# Pallette_Rev1.net
KiCad netlist of a schematic drawn in Altium Designer
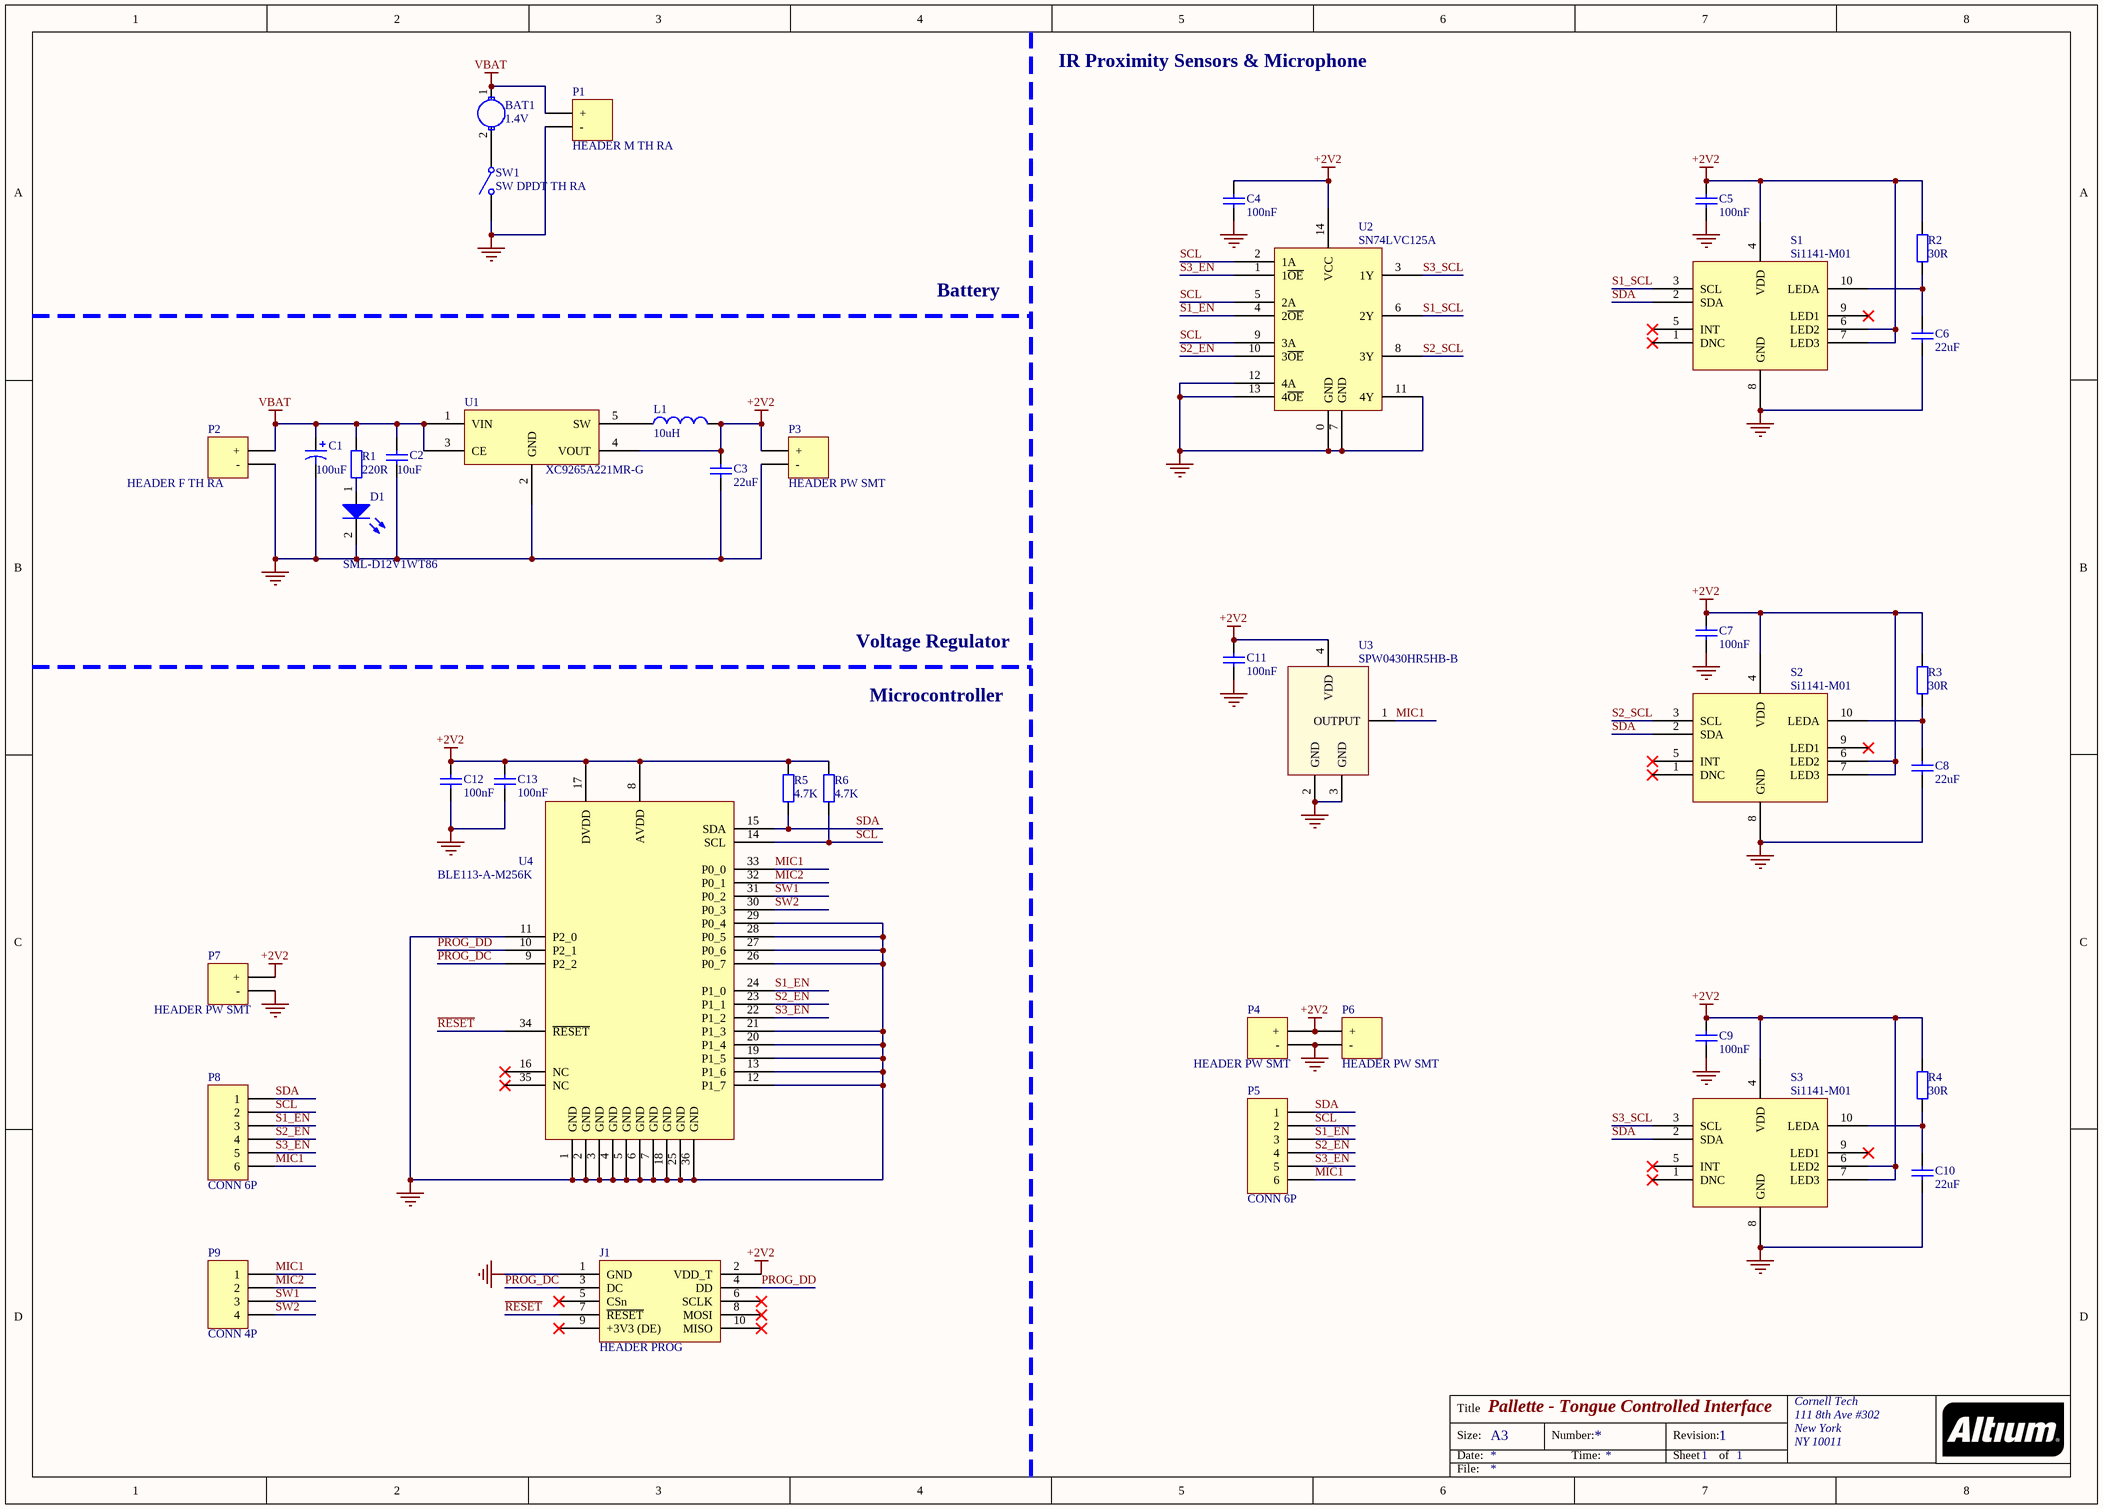
[diagram p0: Pallette_Rev1.SchDoc]

(export (version "E")
  (design (tool "Eeschema 10.0.6"))
  (components
    (comp (ref "BAT1")
      (value "1.4V")
      (footprint "BAT RETAINER 13")
      (description "RETAINER COIN CELL 7.9MM SMD")
      (fields
        (field (name "DIGI-KEY PART NUMBER") "36-2988-ND")
        (field (name "MANUFACTURER") "Keystone Electronics")
      )
      (libsource (lib "Pallette") (part "BAT RETAINER 13"))
    )
    (comp (ref "C1")
      (value "100uF")
      (footprint "1411")
      (description "CAP TANT POLY 100UF 8V 1411")
      (fields
        (field (name "DIGI-KEY PART NUMBER") "P16641CT-ND")
        (field (name "MANUFACTURER") "Panasonic Electronic Components")
      )
      (libsource (lib "Pallette") (part "CAP Pol 100uF"))
    )
    (comp (ref "C2")
      (value "10uF")
      (footprint "0603")
      (description "CAP CER 10UF ±20% 10V X5R 0603")
      (fields
        (field (name "DIGI-KEY PART NUMBER") "490-12734-1-ND")
        (field (name "MANUFACTURER PART NUMBER") "GRM188R61A106MAALD")
      )
      (libsource (lib "Pallette") (part "CAP 10uF"))
    )
    (comp (ref "C3")
      (value "22uF")
      (footprint "0603")
      (description "CAP CER 22UF 6.3V X5R 0603")
      (fields
        (field (name "DIGI-KEY PART NUMBER") "490-7611-1-ND")
        (field (name "MANUFACTURER PART NUMBER") "GRM188R60J226MEA0D")
      )
      (libsource (lib "Pallette") (part "CAP 22uF"))
    )
    (comp (ref "C4")
      (value "100nF")
      (footprint "0402")
      (description "CAP CER 0.1UF 10V X5R 0402")
      (fields (field (name "DIGI-KEY PART NUMBER") "490-1318-1-ND") (field (name "MANUFACTURER") "Murata"))
      (libsource (lib "Pallette") (part "CAP 100nF"))
    )
    (comp (ref "C5")
      (value "100nF")
      (footprint "0402")
      (description "CAP CER 0.1UF 10V X5R 0402")
      (fields (field (name "DIGI-KEY PART NUMBER") "490-1318-1-ND") (field (name "MANUFACTURER") "Murata"))
      (libsource (lib "Pallette") (part "CAP 100nF"))
    )
    (comp (ref "C6")
      (value "22uF")
      (footprint "0603")
      (description "CAP CER 22UF 6.3V X5R 0603")
      (fields
        (field (name "DIGI-KEY PART NUMBER") "490-7611-1-ND")
        (field (name "MANUFACTURER PART NUMBER") "GRM188R60J226MEA0D")
      )
      (libsource (lib "Pallette") (part "CAP 22uF"))
    )
    (comp (ref "C7")
      (value "100nF")
      (footprint "0402")
      (description "CAP CER 0.1UF 10V X5R 0402")
      (fields (field (name "DIGI-KEY PART NUMBER") "490-1318-1-ND") (field (name "MANUFACTURER") "Murata"))
      (libsource (lib "Pallette") (part "CAP 100nF"))
    )
    (comp (ref "C8")
      (value "22uF")
      (footprint "0603")
      (description "CAP CER 22UF 6.3V X5R 0603")
      (fields
        (field (name "DIGI-KEY PART NUMBER") "490-7611-1-ND")
        (field (name "MANUFACTURER PART NUMBER") "GRM188R60J226MEA0D")
      )
      (libsource (lib "Pallette") (part "CAP 22uF"))
    )
    (comp (ref "C9")
      (value "100nF")
      (footprint "0402")
      (description "CAP CER 0.1UF 10V X5R 0402")
      (fields (field (name "DIGI-KEY PART NUMBER") "490-1318-1-ND") (field (name "MANUFACTURER") "Murata"))
      (libsource (lib "Pallette") (part "CAP 100nF"))
    )
    (comp (ref "C10")
      (value "22uF")
      (footprint "0603")
      (description "CAP CER 22UF 6.3V X5R 0603")
      (fields
        (field (name "DIGI-KEY PART NUMBER") "490-7611-1-ND")
        (field (name "MANUFACTURER PART NUMBER") "GRM188R60J226MEA0D")
      )
      (libsource (lib "Pallette") (part "CAP 22uF"))
    )
    (comp (ref "C11")
      (value "100nF")
      (footprint "0402")
      (description "CAP CER 0.1UF 10V X5R 0402")
      (fields (field (name "DIGI-KEY PART NUMBER") "490-1318-1-ND") (field (name "MANUFACTURER") "Murata"))
      (libsource (lib "Pallette") (part "CAP 100nF"))
    )
    (comp (ref "C12")
      (value "100nF")
      (footprint "0402")
      (description "CAP CER 0.1UF 10V X5R 0402")
      (fields (field (name "DIGI-KEY PART NUMBER") "490-1318-1-ND") (field (name "MANUFACTURER") "Murata"))
      (libsource (lib "Pallette") (part "CAP 100nF"))
    )
    (comp (ref "C13")
      (value "100nF")
      (footprint "0402")
      (description "CAP CER 0.1UF 10V X5R 0402")
      (fields (field (name "DIGI-KEY PART NUMBER") "490-1318-1-ND") (field (name "MANUFACTURER") "Murata"))
      (libsource (lib "Pallette") (part "CAP 100nF"))
    )
    (comp (ref "D1")
      (value "SML-D12V1WT86")
      (footprint "LED 0603")
      (description "LED Red 630nm 2.2V Diffused White Lens 0603")
      (fields
        (field (name "MANUFACTURER") "Rohm Semiconductor")
        (field (name "DIGI-KEY PART NUMBER") "SML-D12V1WT86CT-ND")
      )
      (libsource (lib "Pallette") (part "LED SML-D12V1WT86"))
    )
    (comp (ref "J1")
      (value "HEADER PROG")
      (footprint "TC2050-IDC-NL")
      (description "PADS PROGRAMMING")
      (libsource (lib "Pallette") (part "HEADER PROG"))
    )
    (comp (ref "L1")
      (value "10uH")
      (footprint "0805")
      (description "FIXED IND 10UH 500MA 320 MOHM")
      (fields
        (field (name "DIGI-KEY PART NUMBER") "535-12791-1-ND")
        (field (name "MANUFACTURER") "Abracon LLC")
      )
      (libsource (lib "Pallette") (part "IND 10uH"))
    )
    (comp (ref "P1")
      (value "HEADER M TH RA")
      (footprint "PORT PW TH 2P")
      (description "HEADER Male, Unshrouded, 2 Position, 0.100\", Through Hole, Right Angle, Gold")
      (fields (field (name "MANUFACTURER") "3M") (field (name "MANUFACTURER PART NUMBER") "961102-5604-AR"))
      (libsource (lib "Pallette") (part "HEADER PW TH MALE"))
    )
    (comp (ref "P2")
      (value "HEADER F TH RA")
      (footprint "PORT PW TH 2P")
      (description "HEADER Female, 2 Position, 0.100\", Through Hole, Right Angle, Gold")
      (fields
        (field (name "MANUFACTURER PART NUMBER") "PPPC021LGBN-RC")
        (field (name "MANUFACTURER") "Sullins Connector Solutions")
      )
      (libsource (lib "Pallette") (part "HEADER PW TH FEMALE"))
    )
    (comp (ref "P3")
      (value "HEADER PW SMT")
      (footprint "PORT PW SMT 2P")
      (description "Connection Port")
      (fields (field (name "PUBLISHER") "Altium Limited"))
      (libsource (lib "") (part "HEADER PW SMT_1"))
    )
    (comp (ref "P4")
      (value "HEADER PW SMT")
      (footprint "PORT PW SMT 2P")
      (description "Connection Port")
      (fields (field (name "PUBLISHER") "Altium Limited"))
      (libsource (lib "Pallette") (part "HEADER PW SMT"))
    )
    (comp (ref "P5")
      (value "CONN 6P")
      (footprint "PORT CONN 6P")
      (description "Connection Port")
      (fields (field (name "PUBLISHER") "Altium Limited"))
      (libsource (lib "Pallette") (part "HEADER CONN 6P"))
    )
    (comp (ref "P6")
      (value "HEADER PW SMT")
      (footprint "PORT PW SMT 2P")
      (description "Connection Port")
      (fields (field (name "PUBLISHER") "Altium Limited"))
      (libsource (lib "") (part "HEADER PW SMT_1"))
    )
    (comp (ref "P7")
      (value "HEADER PW SMT")
      (footprint "PORT PW SMT 2P")
      (description "Connection Port")
      (fields (field (name "PUBLISHER") "Altium Limited"))
      (libsource (lib "Pallette") (part "HEADER PW SMT"))
    )
    (comp (ref "P8")
      (value "CONN 6P")
      (footprint "PORT CONN 6P")
      (description "Connection Port")
      (fields (field (name "PUBLISHER") "Altium Limited"))
      (libsource (lib "Pallette") (part "HEADER CONN 6P"))
    )
    (comp (ref "P9")
      (value "CONN 4P")
      (footprint "PORT CONN 4P")
      (description "Connection Port")
      (fields (field (name "PUBLISHER") "Altium Limited"))
      (libsource (lib "Pallette") (part "HEADER CONN 4P"))
    )
    (comp (ref "R1")
      (value "220R")
      (footprint "0603")
      (description "RES SMD 220 OHM 1% 1/10W 0603")
      (fields (field (name "DIGI-KEY PART NUMBER") "P220HCT-ND") (field (name "MANUFACTURER") "Panasonic"))
      (libsource (lib "Pallette") (part "RES 220R"))
    )
    (comp (ref "R2")
      (value "30R")
      (footprint "0402")
      (description "RES SMD 30 OHM 1% 1/16W 0402")
      (fields (field (name "DIGI-KEY PART NUMBER") "311-30LRCT-ND") (field (name "MANUFACTURER") "Yageo"))
      (libsource (lib "Pallette") (part "RES 30R"))
    )
    (comp (ref "R3")
      (value "30R")
      (footprint "0402")
      (description "RES SMD 30 OHM 1% 1/16W 0402")
      (fields (field (name "DIGI-KEY PART NUMBER") "311-30LRCT-ND") (field (name "MANUFACTURER") "Yageo"))
      (libsource (lib "Pallette") (part "RES 30R"))
    )
    (comp (ref "R4")
      (value "30R")
      (footprint "0402")
      (description "RES SMD 30 OHM 1% 1/16W 0402")
      (fields (field (name "DIGI-KEY PART NUMBER") "311-30LRCT-ND") (field (name "MANUFACTURER") "Yageo"))
      (libsource (lib "Pallette") (part "RES 30R"))
    )
    (comp (ref "R5")
      (value "4.7K")
      (footprint "0402")
      (description "RES SMD 4.7K OHM 1% 1/16W 0402")
      (fields (field (name "DIGI-KEY PART NUMBER") "311-4.7KLRCT-ND") (field (name "MANUFACTURER") "Yageo"))
      (libsource (lib "Pallette") (part "RES 4.7K"))
    )
    (comp (ref "R6")
      (value "4.7K")
      (footprint "0402")
      (description "RES SMD 4.7K OHM 1% 1/16W 0402")
      (fields (field (name "DIGI-KEY PART NUMBER") "311-4.7KLRCT-ND") (field (name "MANUFACTURER") "Yageo"))
      (libsource (lib "Pallette") (part "RES 4.7K"))
    )
    (comp (ref "S1")
      (value "Si1141-M01")
      (footprint "SI1141-M01")
      (description "SENS IR PROXIMITY AMB LT 10QFN")
      (fields
        (field (name "DIGI-KEY PART NUMBER") "336-3260-1-ND")
        (field (name "MANUFACTURER") "Silicon Labs")
      )
      (libsource (lib "Pallette") (part "SENS Si1141-M01"))
    )
    (comp (ref "S2")
      (value "Si1141-M01")
      (footprint "SI1141-M01")
      (description "SENS IR PROXIMITY AMB LT 10QFN")
      (fields
        (field (name "DIGI-KEY PART NUMBER") "336-3260-1-ND")
        (field (name "MANUFACTURER") "Silicon Labs")
      )
      (libsource (lib "Pallette") (part "SENS Si1141-M01"))
    )
    (comp (ref "S3")
      (value "Si1141-M01")
      (footprint "SI1141-M01")
      (description "SENS IR PROXIMITY AMB LT 10QFN")
      (fields
        (field (name "DIGI-KEY PART NUMBER") "336-3260-1-ND")
        (field (name "MANUFACTURER") "Silicon Labs")
      )
      (libsource (lib "Pallette") (part "SENS Si1141-M01"))
    )
    (comp (ref "SW1")
      (value "SW DPDT TH RA")
      (footprint "SW DPDT TH RA")
      (description "SW Slide Switch DPDT Through Hole, Right Angle")
      (fields
        (field (name "MANUFACTURER") "C&K Components")
        (field (name "MANUFACTURER PART NUMBER") "JS202011AQN")
      )
      (libsource (lib "Pallette") (part "SW DPDT"))
    )
    (comp (ref "U1")
      (value "XC9265A221MR-G")
      (footprint "SOT-25")
      (description "IC REG BUCK 2.2V 0.2A SYNC SOT25")
      (fields
        (field (name "DIGI-KEY PART NUMBER") "893-1305-1-ND")
        (field (name "MANUFACTURER") "Torex Semiconductor Ltd")
      )
      (libsource (lib "Pallette") (part "VR XC9265A221MR-G"))
    )
    (comp (ref "U2")
      (value "SN74LVC125A")
      (footprint "VQFN14")
      (description "IC BUS BUFF TRI-ST QD 14VQFN")
      (fields
        (field (name "MANUFACTURER") "Texas Instruments")
        (field (name "MANUFACTURER PART NUMBER") "SN74LVC125ARGYR")
      )
      (libsource (lib "Pallette") (part "BUFF SN74LVC125A"))
    )
    (comp (ref "U3")
      (value "SPW0430HR5HB-B")
      (footprint "MIC-4P")
      (description "MIC MEMS ANALOG OMNI")
      (fields (field (name "DIGI-KEY PART NUMBER") "423-1215-1-ND") (field (name "MANUFACTURER") "Knowles"))
      (libsource (lib "Pallette") (part "MIC SPW0430HR5HB-B"))
    )
    (comp (ref "U4")
      (value "BLE113-A-M256K")
      (footprint "BLE113-A")
      (description "MODULE BT 4.0 BLE113 OTA")
      (fields
        (field (name "MANUFACTURER") "Silicon Labs")
        (field (name "DIGI-KEY PART NUMBER") "1446-1035-1-ND")
      )
      (libsource (lib "Pallette") (part "uC BLE113"))
    )
  )
  (nets
    (net (code "1") (name "+2V2") (class "Default")
      (node (ref "C11") (pin "1") (pinfunction "1_1") (pintype "passive"))
      (node (ref "C12") (pin "2") (pinfunction "2_2") (pintype "passive"))
      (node (ref "C13") (pin "2") (pinfunction "2_2") (pintype "passive"))
      (node (ref "C3") (pin "2") (pinfunction "2_2") (pintype "passive"))
      (node (ref "C4") (pin "2") (pinfunction "2_2") (pintype "passive"))
      (node (ref "C5") (pin "2") (pinfunction "2_2") (pintype "passive"))
      (node (ref "C7") (pin "2") (pinfunction "2_2") (pintype "passive"))
      (node (ref "C9") (pin "2") (pinfunction "2_2") (pintype "passive"))
      (node (ref "J1") (pin "2") (pinfunction "VDD_T_2") (pintype "passive"))
      (node (ref "L1") (pin "2") (pinfunction "2_2") (pintype "passive"))
      (node (ref "P3") (pin "1") (pinfunction "+_1") (pintype "passive"))
      (node (ref "P4") (pin "1") (pinfunction "+_1") (pintype "passive"))
      (node (ref "P6") (pin "1") (pinfunction "+_1") (pintype "passive"))
      (node (ref "P7") (pin "1") (pinfunction "+_1") (pintype "passive"))
      (node (ref "R2") (pin "2") (pinfunction "2_2") (pintype "passive"))
      (node (ref "R3") (pin "2") (pinfunction "2_2") (pintype "passive"))
      (node (ref "R4") (pin "2") (pinfunction "2_2") (pintype "passive"))
      (node (ref "R5") (pin "2") (pinfunction "2_2") (pintype "passive"))
      (node (ref "R6") (pin "2") (pinfunction "2_2") (pintype "passive"))
      (node (ref "S1") (pin "4") (pinfunction "VDD_4") (pintype "passive"))
      (node (ref "S1") (pin "6") (pinfunction "LED2_6") (pintype "passive"))
      (node (ref "S1") (pin "7") (pinfunction "LED3_7") (pintype "passive"))
      (node (ref "S2") (pin "4") (pinfunction "VDD_4") (pintype "passive"))
      (node (ref "S2") (pin "6") (pinfunction "LED2_6") (pintype "passive"))
      (node (ref "S2") (pin "7") (pinfunction "LED3_7") (pintype "passive"))
      (node (ref "S3") (pin "4") (pinfunction "VDD_4") (pintype "passive"))
      (node (ref "S3") (pin "6") (pinfunction "LED2_6") (pintype "passive"))
      (node (ref "S3") (pin "7") (pinfunction "LED3_7") (pintype "passive"))
      (node (ref "U1") (pin "4") (pinfunction "VOUT_4") (pintype "passive"))
      (node (ref "U2") (pin "14") (pinfunction "VCC_14") (pintype "passive"))
      (node (ref "U3") (pin "4") (pinfunction "VDD_4") (pintype "passive"))
      (node (ref "U4") (pin "17") (pinfunction "DVDD_17") (pintype "passive"))
      (node (ref "U4") (pin "8") (pinfunction "AVDD_8") (pintype "passive"))
    )
    (net (code "2") (name "/MIC1") (class "Default")
      (node (ref "P5") (pin "6") (pinfunction "6_6") (pintype "passive"))
      (node (ref "P8") (pin "6") (pinfunction "6_6") (pintype "passive"))
      (node (ref "P9") (pin "1") (pinfunction "1_1") (pintype "passive"))
      (node (ref "U3") (pin "1") (pinfunction "OUTPUT_1") (pintype "passive"))
      (node (ref "U4") (pin "33") (pinfunction "P0_0_33") (pintype "passive"))
    )
    (net (code "3") (name "/MIC2") (class "Default")
      (node (ref "P9") (pin "2") (pinfunction "2_2") (pintype "passive"))
      (node (ref "U4") (pin "32") (pinfunction "P0_1_32") (pintype "passive"))
    )
    (net (code "4") (name "/PROG_DC") (class "Default")
      (node (ref "J1") (pin "3") (pinfunction "DC_3") (pintype "passive"))
      (node (ref "U4") (pin "9") (pinfunction "P2_2_9") (pintype "passive"))
    )
    (net (code "5") (name "/PROG_DD") (class "Default")
      (node (ref "J1") (pin "4") (pinfunction "DD_4") (pintype "passive"))
      (node (ref "U4") (pin "10") (pinfunction "P2_1_10") (pintype "passive"))
    )
    (net (code "6") (name "/S1_EN") (class "Default")
      (node (ref "P5") (pin "3") (pinfunction "3_3") (pintype "passive"))
      (node (ref "P8") (pin "3") (pinfunction "3_3") (pintype "passive"))
      (node (ref "U2") (pin "4") (pinfunction "2~{OE}_4") (pintype "passive"))
      (node (ref "U4") (pin "24") (pinfunction "P1_0_24") (pintype "passive"))
    )
    (net (code "7") (name "/S1_SCL") (class "Default")
      (node (ref "S1") (pin "3") (pinfunction "SCL_3") (pintype "passive"))
      (node (ref "U2") (pin "6") (pinfunction "2Y_6") (pintype "passive"))
    )
    (net (code "8") (name "/S2_EN") (class "Default")
      (node (ref "P5") (pin "4") (pinfunction "4_4") (pintype "passive"))
      (node (ref "P8") (pin "4") (pinfunction "4_4") (pintype "passive"))
      (node (ref "U2") (pin "10") (pinfunction "3~{OE}_10") (pintype "passive"))
      (node (ref "U4") (pin "23") (pinfunction "P1_1_23") (pintype "passive"))
    )
    (net (code "9") (name "/S2_SCL") (class "Default")
      (node (ref "S2") (pin "3") (pinfunction "SCL_3") (pintype "passive"))
      (node (ref "U2") (pin "8") (pinfunction "3Y_8") (pintype "passive"))
    )
    (net (code "10") (name "/S3_EN") (class "Default")
      (node (ref "P5") (pin "5") (pinfunction "5_5") (pintype "passive"))
      (node (ref "P8") (pin "5") (pinfunction "5_5") (pintype "passive"))
      (node (ref "U2") (pin "1") (pinfunction "1~{OE}_1") (pintype "passive"))
      (node (ref "U4") (pin "22") (pinfunction "P1_2_22") (pintype "passive"))
    )
    (net (code "11") (name "/S3_SCL") (class "Default")
      (node (ref "S3") (pin "3") (pinfunction "SCL_3") (pintype "passive"))
      (node (ref "U2") (pin "3") (pinfunction "1Y_3") (pintype "passive"))
    )
    (net (code "12") (name "/SCL") (class "Default")
      (node (ref "P5") (pin "2") (pinfunction "2_2") (pintype "passive"))
      (node (ref "P8") (pin "2") (pinfunction "2_2") (pintype "passive"))
      (node (ref "R6") (pin "1") (pinfunction "1_1") (pintype "passive"))
      (node (ref "U2") (pin "2") (pinfunction "1A_2") (pintype "passive"))
      (node (ref "U2") (pin "5") (pinfunction "2A_5") (pintype "passive"))
      (node (ref "U2") (pin "9") (pinfunction "3A_9") (pintype "passive"))
      (node (ref "U4") (pin "14") (pinfunction "SCL_14") (pintype "passive"))
    )
    (net (code "13") (name "/SDA") (class "Default")
      (node (ref "P5") (pin "1") (pinfunction "1_1") (pintype "passive"))
      (node (ref "P8") (pin "1") (pinfunction "1_1") (pintype "passive"))
      (node (ref "R5") (pin "1") (pinfunction "1_1") (pintype "passive"))
      (node (ref "S1") (pin "2") (pinfunction "SDA_2") (pintype "passive"))
      (node (ref "S2") (pin "2") (pinfunction "SDA_2") (pintype "passive"))
      (node (ref "S3") (pin "2") (pinfunction "SDA_2") (pintype "passive"))
      (node (ref "U4") (pin "15") (pinfunction "SDA_15") (pintype "passive"))
    )
    (net (code "14") (name "/SW1") (class "Default")
      (node (ref "P9") (pin "3") (pinfunction "3_3") (pintype "passive"))
      (node (ref "U4") (pin "31") (pinfunction "P0_2_31") (pintype "passive"))
    )
    (net (code "15") (name "/SW2") (class "Default")
      (node (ref "P9") (pin "4") (pinfunction "4_4") (pintype "passive"))
      (node (ref "U4") (pin "30") (pinfunction "P0_3_30") (pintype "passive"))
    )
    (net (code "16") (name "/~{RESET}") (class "Default")
      (node (ref "J1") (pin "7") (pinfunction "~{RESET}_7") (pintype "passive"))
      (node (ref "U4") (pin "34") (pinfunction "~{RESET}_34") (pintype "passive"))
    )
    (net (code "17") (name "GND") (class "Default")
      (node (ref "C1") (pin "2") (pinfunction "2_2") (pintype "passive"))
      (node (ref "C10") (pin "1") (pinfunction "1_1") (pintype "passive"))
      (node (ref "C11") (pin "2") (pinfunction "2_2") (pintype "passive"))
      (node (ref "C12") (pin "1") (pinfunction "1_1") (pintype "passive"))
      (node (ref "C13") (pin "1") (pinfunction "1_1") (pintype "passive"))
      (node (ref "C2") (pin "1") (pinfunction "1_1") (pintype "passive"))
      (node (ref "C3") (pin "1") (pinfunction "1_1") (pintype "passive"))
      (node (ref "C4") (pin "1") (pinfunction "1_1") (pintype "passive"))
      (node (ref "C5") (pin "1") (pinfunction "1_1") (pintype "passive"))
      (node (ref "C6") (pin "1") (pinfunction "1_1") (pintype "passive"))
      (node (ref "C7") (pin "1") (pinfunction "1_1") (pintype "passive"))
      (node (ref "C8") (pin "1") (pinfunction "1_1") (pintype "passive"))
      (node (ref "C9") (pin "1") (pinfunction "1_1") (pintype "passive"))
      (node (ref "D1") (pin "2") (pinfunction "K_2") (pintype "passive"))
      (node (ref "J1") (pin "1") (pinfunction "GND_1") (pintype "passive"))
      (node (ref "P1") (pin "2") (pinfunction "-_2") (pintype "passive"))
      (node (ref "P2") (pin "2") (pinfunction "-_2") (pintype "passive"))
      (node (ref "P3") (pin "2") (pinfunction "-_2") (pintype "passive"))
      (node (ref "P4") (pin "2") (pinfunction "-_2") (pintype "passive"))
      (node (ref "P6") (pin "2") (pinfunction "-_2") (pintype "passive"))
      (node (ref "P7") (pin "2") (pinfunction "-_2") (pintype "passive"))
      (node (ref "S1") (pin "8") (pinfunction "GND_8") (pintype "passive"))
      (node (ref "S2") (pin "8") (pinfunction "GND_8") (pintype "passive"))
      (node (ref "S3") (pin "8") (pinfunction "GND_8") (pintype "passive"))
      (node (ref "SW1") (pin "2") (pinfunction "NO_2") (pintype "passive"))
      (node (ref "U1") (pin "2") (pinfunction "GND_2") (pintype "passive"))
      (node (ref "U2") (pin "0") (pinfunction "GND_0") (pintype "passive"))
      (node (ref "U2") (pin "11") (pinfunction "4Y_11") (pintype "passive"))
      (node (ref "U2") (pin "12") (pinfunction "4A_12") (pintype "passive"))
      (node (ref "U2") (pin "13") (pinfunction "4~{OE}_13") (pintype "passive"))
      (node (ref "U2") (pin "7") (pinfunction "GND_7") (pintype "passive"))
      (node (ref "U3") (pin "2") (pinfunction "GND_2") (pintype "passive"))
      (node (ref "U3") (pin "3") (pinfunction "GND_3") (pintype "passive"))
      (node (ref "U4") (pin "1") (pinfunction "GND_1") (pintype "passive"))
      (node (ref "U4") (pin "11") (pinfunction "P2_0_11") (pintype "passive"))
      (node (ref "U4") (pin "12") (pinfunction "P1_7_12") (pintype "passive"))
      (node (ref "U4") (pin "13") (pinfunction "P1_6_13") (pintype "passive"))
      (node (ref "U4") (pin "18") (pinfunction "GND_18") (pintype "passive"))
      (node (ref "U4") (pin "19") (pinfunction "P1_5_19") (pintype "passive"))
      (node (ref "U4") (pin "2") (pinfunction "GND_2") (pintype "passive"))
      (node (ref "U4") (pin "20") (pinfunction "P1_4_20") (pintype "passive"))
      (node (ref "U4") (pin "21") (pinfunction "P1_3_21") (pintype "passive"))
      (node (ref "U4") (pin "25") (pinfunction "GND_25") (pintype "passive"))
      (node (ref "U4") (pin "26") (pinfunction "P0_7_26") (pintype "passive"))
      (node (ref "U4") (pin "27") (pinfunction "P0_6_27") (pintype "passive"))
      (node (ref "U4") (pin "28") (pinfunction "P0_5_28") (pintype "passive"))
      (node (ref "U4") (pin "29") (pinfunction "P0_4_29") (pintype "passive"))
      (node (ref "U4") (pin "3") (pinfunction "GND_3") (pintype "passive"))
      (node (ref "U4") (pin "36") (pinfunction "GND_36") (pintype "passive"))
      (node (ref "U4") (pin "4") (pinfunction "GND_4") (pintype "passive"))
      (node (ref "U4") (pin "5") (pinfunction "GND_5") (pintype "passive"))
      (node (ref "U4") (pin "6") (pinfunction "GND_6") (pintype "passive"))
      (node (ref "U4") (pin "7") (pinfunction "GND_7") (pintype "passive"))
    )
    (net (code "18") (name "Net-(BAT1--)") (class "Default")
      (node (ref "BAT1") (pin "2") (pinfunction "-_2") (pintype "passive"))
      (node (ref "SW1") (pin "1") (pinfunction "COMMON_1") (pintype "passive"))
    )
    (net (code "19") (name "Net-(D1-A)") (class "Default")
      (node (ref "D1") (pin "1") (pinfunction "A_1") (pintype "passive"))
      (node (ref "R1") (pin "1") (pinfunction "1_1") (pintype "passive"))
    )
    (net (code "20") (name "Net-(S1-LEDA)") (class "Default")
      (node (ref "C6") (pin "2") (pinfunction "2_2") (pintype "passive"))
      (node (ref "R2") (pin "1") (pinfunction "1_1") (pintype "passive"))
      (node (ref "S1") (pin "10") (pinfunction "LEDA_10") (pintype "passive"))
    )
    (net (code "21") (name "Net-(S2-LEDA)") (class "Default")
      (node (ref "C8") (pin "2") (pinfunction "2_2") (pintype "passive"))
      (node (ref "R3") (pin "1") (pinfunction "1_1") (pintype "passive"))
      (node (ref "S2") (pin "10") (pinfunction "LEDA_10") (pintype "passive"))
    )
    (net (code "22") (name "Net-(S3-LEDA)") (class "Default")
      (node (ref "C10") (pin "2") (pinfunction "2_2") (pintype "passive"))
      (node (ref "R4") (pin "1") (pinfunction "1_1") (pintype "passive"))
      (node (ref "S3") (pin "10") (pinfunction "LEDA_10") (pintype "passive"))
    )
    (net (code "23") (name "Net-(U1-SW)") (class "Default")
      (node (ref "L1") (pin "1") (pinfunction "1_1") (pintype "passive"))
      (node (ref "U1") (pin "5") (pinfunction "SW_5") (pintype "passive"))
    )
    (net (code "24") (name "VBAT") (class "Default")
      (node (ref "BAT1") (pin "1") (pinfunction "+_1") (pintype "passive"))
      (node (ref "C1") (pin "1") (pinfunction "1_1") (pintype "passive"))
      (node (ref "C2") (pin "2") (pinfunction "2_2") (pintype "passive"))
      (node (ref "P1") (pin "1") (pinfunction "+_1") (pintype "passive"))
      (node (ref "P2") (pin "1") (pinfunction "+_1") (pintype "passive"))
      (node (ref "R1") (pin "2") (pinfunction "2_2") (pintype "passive"))
      (node (ref "U1") (pin "1") (pinfunction "VIN_1") (pintype "passive"))
      (node (ref "U1") (pin "3") (pinfunction "CE_3") (pintype "passive"))
    )
    (net (code "25") (name "unconnected-(J1-+3V3_(DE)-Pad9)") (class "Default")
      (node (ref "J1") (pin "9") (pinfunction "+3V3_(DE)_9") (pintype "passive+no_connect"))
    )
    (net (code "26") (name "unconnected-(J1-CSn-Pad5)") (class "Default")
      (node (ref "J1") (pin "5") (pinfunction "CSn_5") (pintype "passive+no_connect"))
    )
    (net (code "27") (name "unconnected-(J1-MISO-Pad10)") (class "Default")
      (node (ref "J1") (pin "10") (pinfunction "MISO_10") (pintype "passive+no_connect"))
    )
    (net (code "28") (name "unconnected-(J1-MOSI-Pad8)") (class "Default")
      (node (ref "J1") (pin "8") (pinfunction "MOSI_8") (pintype "passive+no_connect"))
    )
    (net (code "29") (name "unconnected-(J1-SCLK-Pad6)") (class "Default")
      (node (ref "J1") (pin "6") (pinfunction "SCLK_6") (pintype "passive+no_connect"))
    )
    (net (code "30") (name "unconnected-(S1-DNC-Pad1)") (class "Default")
      (node (ref "S1") (pin "1") (pinfunction "DNC_1") (pintype "passive+no_connect"))
    )
    (net (code "31") (name "unconnected-(S1-INT-Pad5)") (class "Default")
      (node (ref "S1") (pin "5") (pinfunction "INT_5") (pintype "passive+no_connect"))
    )
    (net (code "32") (name "unconnected-(S1-LED1-Pad9)") (class "Default")
      (node (ref "S1") (pin "9") (pinfunction "LED1_9") (pintype "passive+no_connect"))
    )
    (net (code "33") (name "unconnected-(S2-DNC-Pad1)") (class "Default")
      (node (ref "S2") (pin "1") (pinfunction "DNC_1") (pintype "passive+no_connect"))
    )
    (net (code "34") (name "unconnected-(S2-INT-Pad5)") (class "Default")
      (node (ref "S2") (pin "5") (pinfunction "INT_5") (pintype "passive+no_connect"))
    )
    (net (code "35") (name "unconnected-(S2-LED1-Pad9)") (class "Default")
      (node (ref "S2") (pin "9") (pinfunction "LED1_9") (pintype "passive+no_connect"))
    )
    (net (code "36") (name "unconnected-(S3-DNC-Pad1)") (class "Default")
      (node (ref "S3") (pin "1") (pinfunction "DNC_1") (pintype "passive+no_connect"))
    )
    (net (code "37") (name "unconnected-(S3-INT-Pad5)") (class "Default")
      (node (ref "S3") (pin "5") (pinfunction "INT_5") (pintype "passive+no_connect"))
    )
    (net (code "38") (name "unconnected-(S3-LED1-Pad9)") (class "Default")
      (node (ref "S3") (pin "9") (pinfunction "LED1_9") (pintype "passive+no_connect"))
    )
    (net (code "39") (name "unconnected-(U4-NC-Pad16)") (class "Default")
      (node (ref "U4") (pin "16") (pinfunction "NC_16") (pintype "passive+no_connect"))
    )
    (net (code "40") (name "unconnected-(U4-NC-Pad35)") (class "Default")
      (node (ref "U4") (pin "35") (pinfunction "NC_35") (pintype "passive+no_connect"))
    )
  )
)
